# Screen.net
KiCad netlist of a schematic drawn in Altium Designer
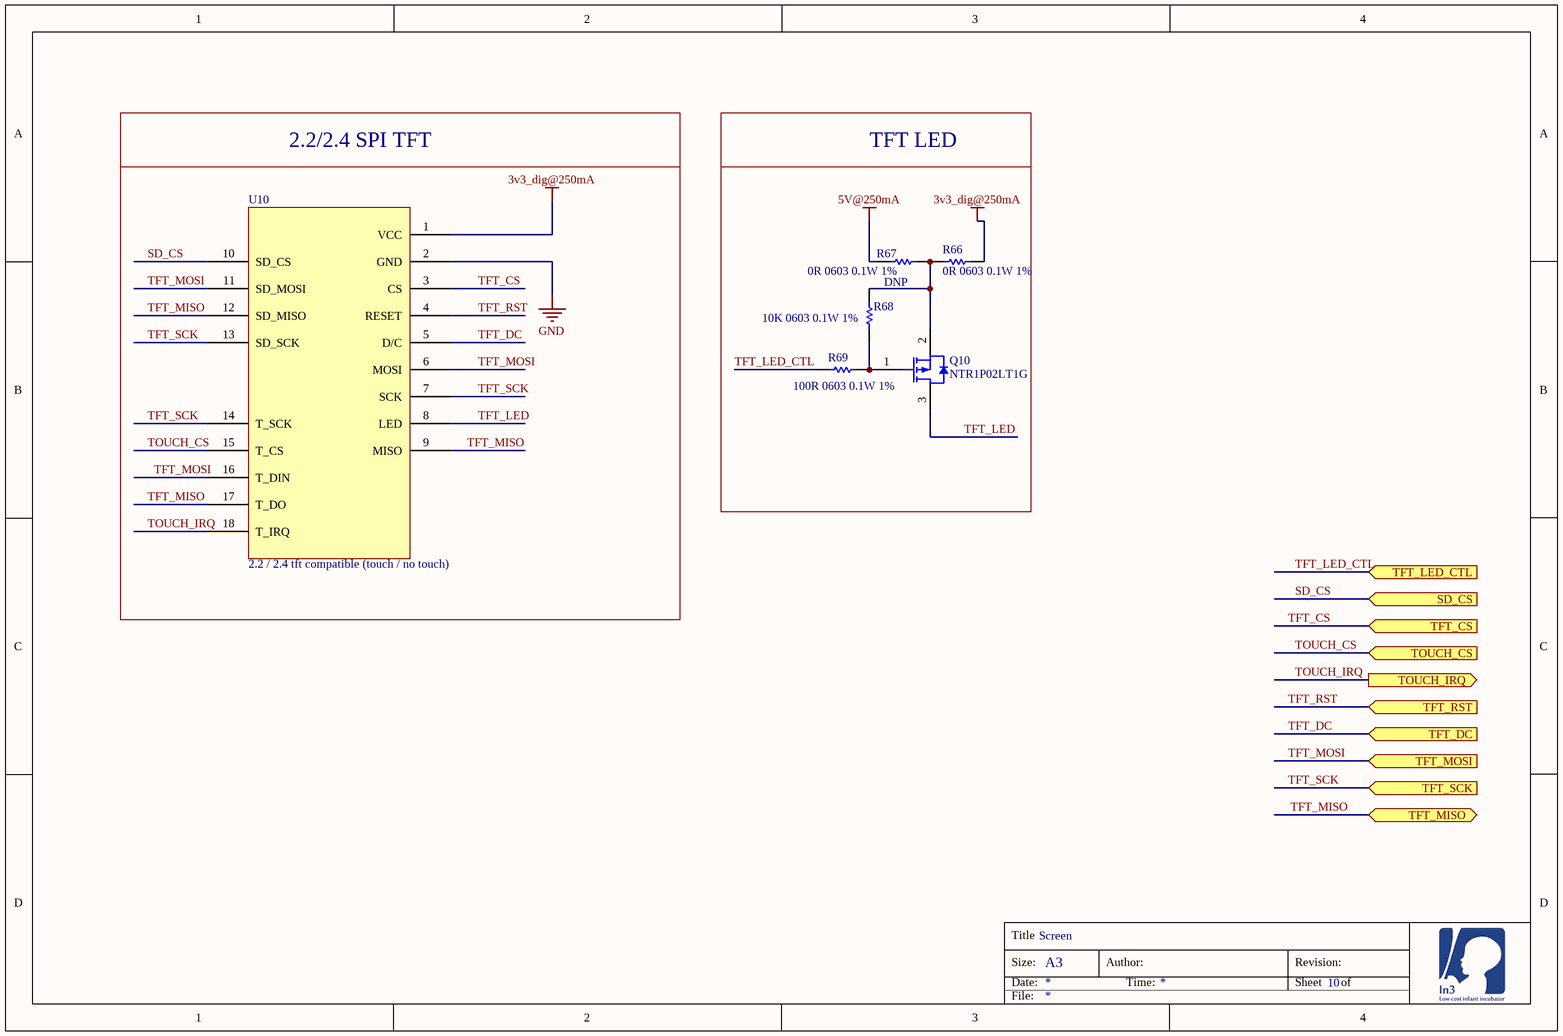
[diagram p0: Screen.SchDoc]

(export (version "E")
  (design (tool "Eeschema 10.0.6"))
  (components
    (comp (ref "Q10")
      (value "NTR1P02LT1G")
      (footprint "ONSC-SOT-23-3-318-08_V")
      (description "Power MOSFET, -20 V, -1.3 A, P-Channel, 3-Pin SOT-23, Pb-Free, Tape and Reel")
      (libsource (lib "CommunityVault") (part "ONSC-PMOS-G1S2D3-3_D"))
    )
    (comp (ref "R66")
      (value "0R 0603 0.1W 1%")
      (footprint "RESC1609X55X30ML10T20")
      (libsource (lib "CommunityVault") (part "CMP-536b9a7387ce8cac-10"))
    )
    (comp (ref "R67")
      (value "0R 0603 0.1W 1%")
      (footprint "RESC1609X55X30ML10T20")
      (fields (field (name "DNP") "DNP"))
      (libsource (lib "CommunityVault") (part "CMP-536b9a7387ce8cac-10"))
    )
    (comp (ref "R68")
      (value "10K 0603 0.1W 1%")
      (footprint "RESC1609X55X30ML10T20")
      (description "30K 0603 0.1W 1%")
      (fields (field (name "TOLERANCE") "1%"))
      (libsource (lib "CommunityVault") (part "CMP-4716590-9"))
    )
    (comp (ref "R69")
      (value "100R 0603 0.1W 1%")
      (footprint "RESC1609X55X30ML10T20")
      (fields (field (name "MANUFACTURER PART NUMBER") "CR0603-FX-1001ELF"))
      (libsource (lib "CommunityVault") (part "CMP-a61f6f36030f79d8-4"))
    )
    (comp (ref "U10")
      (value "2.2 / 2.4 tft compatible (touch / no touch)")
      (footprint "PCB-3toksntatosxbsuzovrj-1")
      (description "TZT 2.4\" 240x320 SPI TFT LCD Serial Port Module+5V/3.3V PBC Adapter Micro SD ILI9341")
      (libsource (lib "FavoritesLibrary") (part "SYM-m0xp0jkbbaqlzhag27re-1"))
    )
  )
  (nets
    (net (code "1") (name "/SD_CS") (class "Default")
      (node (ref "U10") (pin "10") (pinfunction "SD_CS_10") (pintype "passive"))
    )
    (net (code "2") (name "/TFT_CS") (class "Default")
      (node (ref "U10") (pin "3") (pinfunction "CS_3") (pintype "passive"))
    )
    (net (code "3") (name "/TFT_DC") (class "Default")
      (node (ref "U10") (pin "5") (pinfunction "D/C_5") (pintype "passive"))
    )
    (net (code "4") (name "/TFT_LED") (class "Default")
      (node (ref "Q10") (pin "3") (pinfunction "D_3") (pintype "passive"))
      (node (ref "U10") (pin "8") (pinfunction "LED_8") (pintype "passive"))
    )
    (net (code "5") (name "/TFT_LED_CTL") (class "Default")
      (node (ref "R69") (pin "2") (pinfunction "2_2") (pintype "passive"))
    )
    (net (code "6") (name "/TFT_MISO") (class "Default")
      (node (ref "U10") (pin "12") (pinfunction "SD_MISO_12") (pintype "passive"))
      (node (ref "U10") (pin "17") (pinfunction "T_DO_17") (pintype "passive"))
      (node (ref "U10") (pin "9") (pinfunction "MISO_9") (pintype "passive"))
    )
    (net (code "7") (name "/TFT_MOSI") (class "Default")
      (node (ref "U10") (pin "11") (pinfunction "SD_MOSI_11") (pintype "passive"))
      (node (ref "U10") (pin "16") (pinfunction "T_DIN_16") (pintype "passive"))
      (node (ref "U10") (pin "6") (pinfunction "MOSI_6") (pintype "passive"))
    )
    (net (code "8") (name "/TFT_RST") (class "Default")
      (node (ref "U10") (pin "4") (pinfunction "RESET_4") (pintype "passive"))
    )
    (net (code "9") (name "/TFT_SCK") (class "Default")
      (node (ref "U10") (pin "13") (pinfunction "SD_SCK_13") (pintype "passive"))
      (node (ref "U10") (pin "14") (pinfunction "T_SCK_14") (pintype "passive"))
      (node (ref "U10") (pin "7") (pinfunction "SCK_7") (pintype "passive"))
    )
    (net (code "10") (name "/TOUCH_CS") (class "Default")
      (node (ref "U10") (pin "15") (pinfunction "T_CS_15") (pintype "passive"))
    )
    (net (code "11") (name "/TOUCH_IRQ") (class "Default")
      (node (ref "U10") (pin "18") (pinfunction "T_IRQ_18") (pintype "passive"))
    )
    (net (code "12") (name "3v3_dig@250mA") (class "Default")
      (node (ref "R66") (pin "2") (pinfunction "2_2") (pintype "passive"))
      (node (ref "U10") (pin "1") (pinfunction "VCC_1") (pintype "passive"))
    )
    (net (code "13") (name "5V@250mA") (class "Default")
      (node (ref "R67") (pin "1") (pinfunction "1_1") (pintype "passive"))
    )
    (net (code "14") (name "GND") (class "Default")
      (node (ref "U10") (pin "2") (pinfunction "GND_2") (pintype "passive"))
    )
    (net (code "15") (name "Net-(Q10-G)") (class "Default")
      (node (ref "Q10") (pin "1") (pinfunction "G_1") (pintype "passive"))
      (node (ref "R68") (pin "1") (pinfunction "1_1") (pintype "passive"))
      (node (ref "R69") (pin "1") (pinfunction "1_1") (pintype "passive"))
    )
    (net (code "16") (name "Net-(Q10-S)") (class "Default")
      (node (ref "Q10") (pin "2") (pinfunction "S_2") (pintype "passive"))
      (node (ref "R66") (pin "1") (pinfunction "1_1") (pintype "passive"))
      (node (ref "R67") (pin "2") (pinfunction "2_2") (pintype "passive"))
      (node (ref "R68") (pin "2") (pinfunction "2_2") (pintype "passive"))
    )
  )
)
